# USBandBatteryCharger.net
KiCad netlist of a schematic drawn in Altium Designer
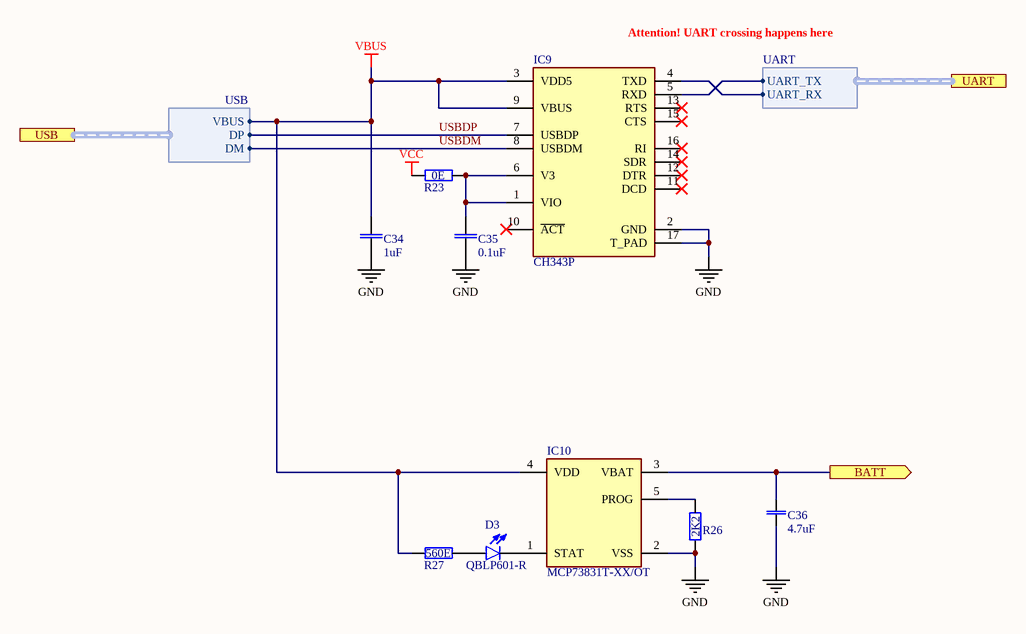
[diagram p0: USBandBatteryCharger.SchDoc]

(export (version "E")
  (design (tool "Eeschema 10.0.6"))
  (components
    (comp (ref "C34")
      (value "1uF")
      (footprint "CAP0402")
      (fields (field (name "MANUFACTURER") "Samsung Electro-Mechanics"))
      (libsource (lib "Schematic") (part "CAP_0402"))
    )
    (comp (ref "C35")
      (value "0.1uF")
      (footprint "CAP0402")
      (fields (field (name "MANUFACTURER") "Samsung Electro-Mechanics"))
      (libsource (lib "Schematic") (part "CAP_0402"))
    )
    (comp (ref "C36")
      (value "4.7uF")
      (footprint "0805")
      (fields (field (name "PART NUMBER") "000090") (field (name "MANUFACTURER") "Samsung Electro-Mechanics"))
      (libsource (lib "TychosLibrary") (part "Capacitor"))
    )
    (comp (ref "D3")
      (value "QBLP601-R")
      (footprint "LED0603")
      (fields (field (name "MANUFACTURER") "QT Brightek (QTB)"))
      (libsource (lib "Schematic") (part "QBLP601-R"))
    )
    (comp (ref "IC9")
      (value "CH343P")
      (footprint "QFN16_3X3")
      (fields (field (name "MANUFACTURER") "WCH") (field (name "JLCPCB PART #") "C2846043"))
      (libsource (lib "Schematic") (part "CH343P"))
    )
    (comp (ref "IC10")
      (value "MCP73831T-XX/OT")
      (footprint "SOT23-5(MCP73831)")
      (fields (field (name "MANUFACTURER") "Microchip Technology"))
      (libsource (lib "Schematic") (part "MCP73831"))
    )
    (comp (ref "R23")
      (value "0E")
      (footprint "RES0402")
      (fields (field (name "MANUFACTURER") "YAGEO"))
      (libsource (lib "Schematic") (part "RES_0402"))
    )
    (comp (ref "R26")
      (value "2K2")
      (footprint "RES0402")
      (fields (field (name "MANUFACTURER") "YAGEO"))
      (libsource (lib "Schematic") (part "RES_0402"))
    )
    (comp (ref "R27")
      (value "560E")
      (footprint "RES0402")
      (fields (field (name "MANUFACTURER") "YAGEO"))
      (libsource (lib "Schematic") (part "RES_0402"))
    )
  )
  (nets
    (net (code "3") (name "/BATT") (class "Default")
      (node (ref "C36") (pin "2") (pinfunction "2_2") (pintype "passive"))
      (node (ref "IC10") (pin "3") (pinfunction "VBAT_3") (pintype "passive"))
    )
    (net (code "4") (name "/UART_RX") (class "Default")
      (node (ref "IC9") (pin "4") (pinfunction "TXD_4") (pintype "passive"))
    )
    (net (code "5") (name "/UART_TX") (class "Default")
      (node (ref "IC9") (pin "5") (pinfunction "RXD_5") (pintype "passive"))
    )
    (net (code "6") (name "/USBDM") (class "Default")
      (node (ref "IC9") (pin "8") (pinfunction "USBDM_8") (pintype "passive"))
    )
    (net (code "7") (name "/USBDP") (class "Default")
      (node (ref "IC9") (pin "7") (pinfunction "USBDP_7") (pintype "passive"))
    )
    (net (code "10") (name "GND") (class "Default")
      (node (ref "C34") (pin "2") (pinfunction "2_2") (pintype "passive"))
      (node (ref "C35") (pin "1") (pinfunction "1_1") (pintype "passive"))
      (node (ref "C36") (pin "1") (pinfunction "1_1") (pintype "passive"))
      (node (ref "IC10") (pin "2") (pinfunction "VSS_2") (pintype "passive"))
      (node (ref "IC9") (pin "17") (pinfunction "T_PAD_17") (pintype "passive"))
      (node (ref "IC9") (pin "2") (pinfunction "GND_2") (pintype "passive"))
      (node (ref "R26") (pin "1") (pinfunction "1_1") (pintype "passive"))
    )
    (net (code "11") (name "Net-(D3-Pad1)") (class "Default")
      (node (ref "D3") (pin "1") (pinfunction "1_1") (pintype "passive"))
      (node (ref "R27") (pin "2") (pinfunction "2_2") (pintype "passive"))
    )
    (net (code "12") (name "Net-(IC9-V3)") (class "Default")
      (node (ref "C35") (pin "2") (pinfunction "2_2") (pintype "passive"))
      (node (ref "IC9") (pin "1") (pinfunction "VIO_1") (pintype "passive"))
      (node (ref "IC9") (pin "6") (pinfunction "V3_6") (pintype "passive"))
      (node (ref "R23") (pin "2") (pinfunction "2_2") (pintype "passive"))
    )
    (net (code "13") (name "Net-(IC10-PROG)") (class "Default")
      (node (ref "IC10") (pin "5") (pinfunction "PROG_5") (pintype "passive"))
      (node (ref "R26") (pin "2") (pinfunction "2_2") (pintype "passive"))
    )
    (net (code "14") (name "Net-(IC10-STAT)") (class "Default")
      (node (ref "D3") (pin "2") (pinfunction "2_2") (pintype "passive"))
      (node (ref "IC10") (pin "1") (pinfunction "STAT_1") (pintype "passive"))
    )
    (net (code "15") (name "VBUS") (class "Default")
      (node (ref "C34") (pin "1") (pinfunction "1_1") (pintype "passive"))
      (node (ref "IC10") (pin "4") (pinfunction "VDD_4") (pintype "passive"))
      (node (ref "IC9") (pin "3") (pinfunction "VDD5_3") (pintype "passive"))
      (node (ref "IC9") (pin "9") (pinfunction "VBUS_9") (pintype "passive"))
      (node (ref "R27") (pin "1") (pinfunction "1_1") (pintype "passive"))
    )
    (net (code "16") (name "VCC") (class "Default")
      (node (ref "R23") (pin "1") (pinfunction "1_1") (pintype "passive"))
    )
    (net (code "17") (name "unconnected-(IC9-CTS-Pad15)") (class "Default")
      (node (ref "IC9") (pin "15") (pinfunction "CTS_15") (pintype "passive+no_connect"))
    )
    (net (code "18") (name "unconnected-(IC9-DCD-Pad11)") (class "Default")
      (node (ref "IC9") (pin "11") (pinfunction "DCD_11") (pintype "passive+no_connect"))
    )
    (net (code "19") (name "unconnected-(IC9-DTR-Pad12)") (class "Default")
      (node (ref "IC9") (pin "12") (pinfunction "DTR_12") (pintype "passive+no_connect"))
    )
    (net (code "20") (name "unconnected-(IC9-RI-Pad16)") (class "Default")
      (node (ref "IC9") (pin "16") (pinfunction "RI_16") (pintype "passive+no_connect"))
    )
    (net (code "21") (name "unconnected-(IC9-RTS-Pad13)") (class "Default")
      (node (ref "IC9") (pin "13") (pinfunction "RTS_13") (pintype "passive+no_connect"))
    )
    (net (code "22") (name "unconnected-(IC9-SDR-Pad14)") (class "Default")
      (node (ref "IC9") (pin "14") (pinfunction "SDR_14") (pintype "passive+no_connect"))
    )
    (net (code "23") (name "unconnected-(IC9-~{ACT}-Pad10)") (class "Default")
      (node (ref "IC9") (pin "10") (pinfunction "~{ACT}_10") (pintype "passive+no_connect"))
    )
  )
)
